# H_bridge_v2.net
KiCad netlist of a schematic drawn in Altium Designer
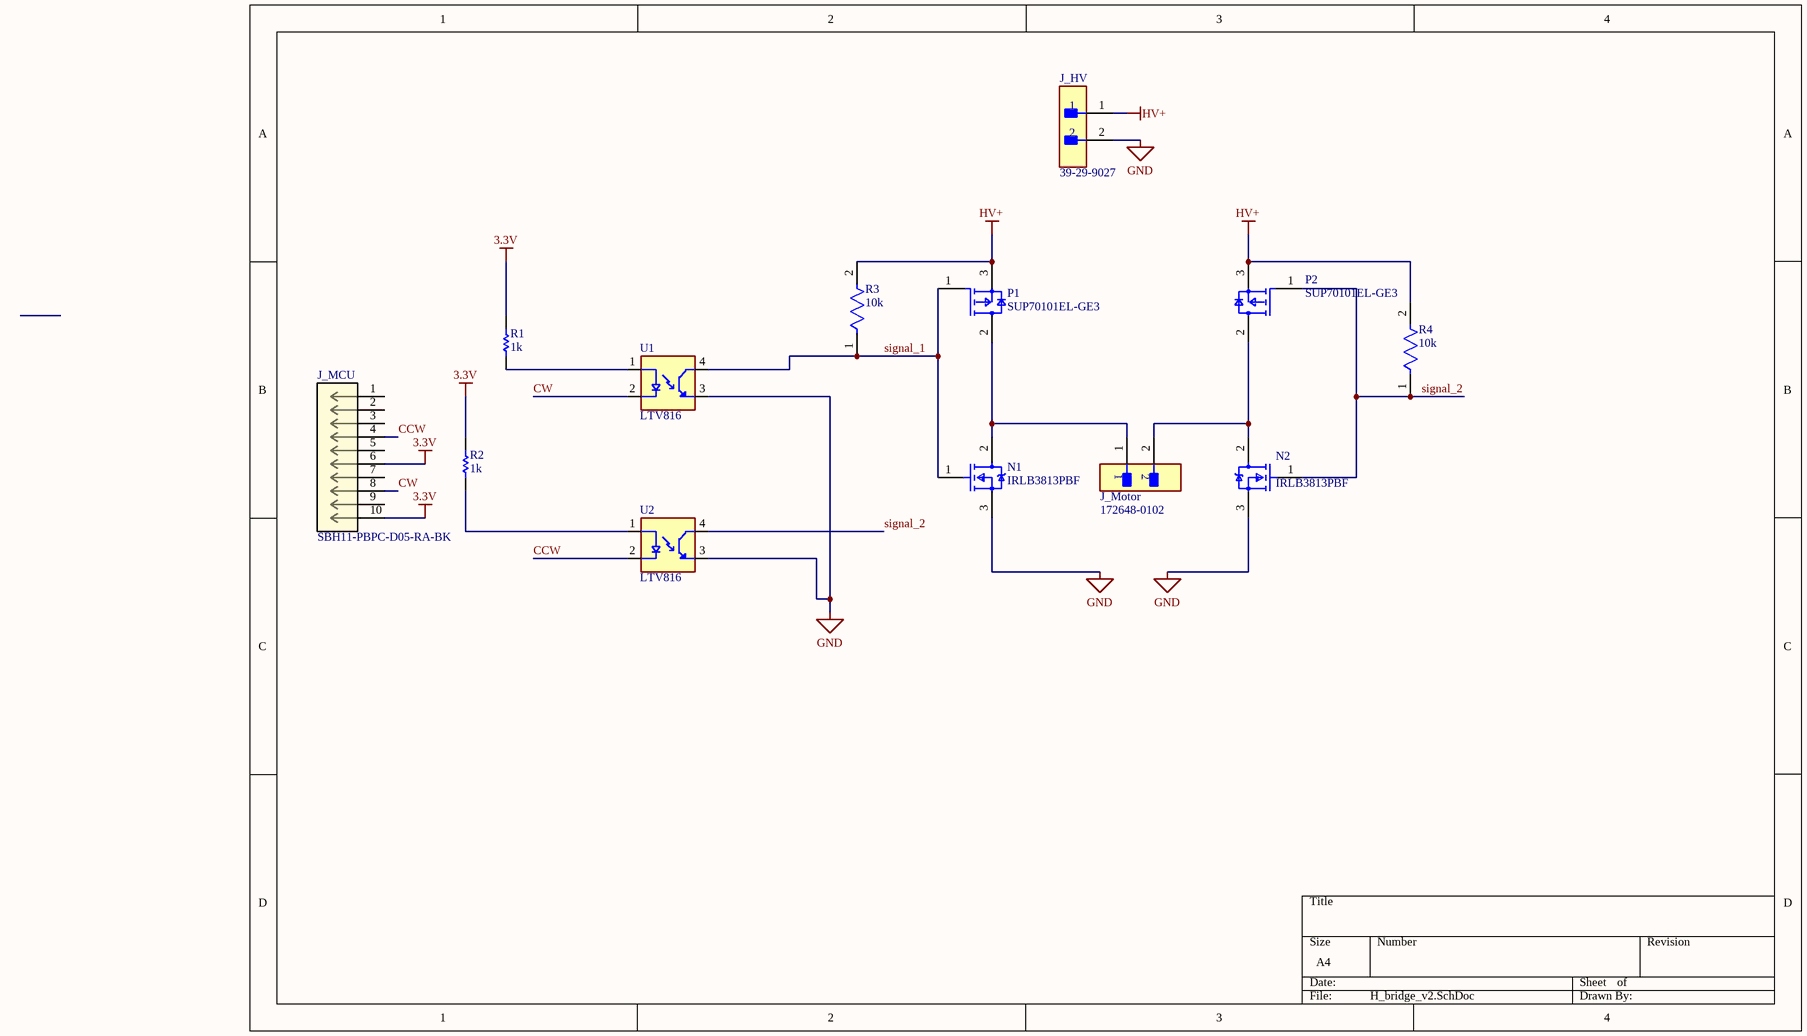
[diagram p0: H_bridge_v2.SchDoc]

(export (version "E")
  (design (tool "Eeschema 10.0.6"))
  (components
    (comp (ref "J_HV")
      (value "39-29-9027")
      (footprint "FP-39-29-9027-MFG")
      (description "CONN HEADER VERT 2POS")
      (libsource (lib "Altium Content Vault") (part "3bc925449376181038e59eaffc5286c"))
    )
    (comp (ref "J_MCU")
      (value "SBH11-PBPC-D05-RA-BK")
      (footprint "CONN10_D05-RA-BK_SUL")
      (description "Description")
      (fields (field (name "COPYRIGHT") "Copyright (C) 2026 Ultra Librarian. All rights reserved."))
      (libsource (lib "SBH11-PBPC-D05-RA-BK_MINE") (part "SBH11-PBPC-D05-RA-BK"))
    )
    (comp (ref "J_Motor")
      (value "172648-0102")
      (footprint "FP-172648-0102-MFG")
      (description "CONN HEADER R/A 2POS 4.2MM")
      (libsource (lib "Altium Content Vault") (part "88c1139f9d239099ffebecbe3f7647a"))
    )
    (comp (ref "N1")
      (value "IRLB3813PBF")
      (footprint "FP-PG-TO220-3-MFG")
      (description "MOSFET N-CH 30V 260A TO-220AB")
      (fields
        (field (name "OCTOPART") "https://octopart.com/irlb3813pbf-infineon-65874923")
        (field (name "MANUFACTURER") "Infineon")
      )
      (libsource (lib "Altium Content Vault") (part "b09f7f152735e370c1ea22a33fa83d6"))
    )
    (comp (ref "N2")
      (value "IRLB3813PBF")
      (footprint "FP-PG-TO220-3-MFG")
      (description "MOSFET N-CH 30V 260A TO-220AB")
      (fields
        (field (name "OCTOPART") "https://octopart.com/irlb3813pbf-infineon-65874923")
        (field (name "MANUFACTURER") "Infineon")
      )
      (libsource (lib "Altium Content Vault") (part "b09f7f152735e370c1ea22a33fa83d6"))
    )
    (comp (ref "P1")
      (value "SUP70101EL-GE3")
      (footprint "FP-SUP70101EL-GE3-MFG")
      (description "MOSFET P-CH 100V 120A TO220AB")
      (fields
        (field (name "OCTOPART") "https://octopart.com/sup70101el-ge3-vishay-82190902")
        (field (name "MANUFACTURER") "Vishay")
      )
      (libsource (lib "Altium Content Vault") (part "63ad6933b9e4fbdba174d6934cad31e"))
    )
    (comp (ref "P2")
      (value "SUP70101EL-GE3")
      (footprint "FP-SUP70101EL-GE3-MFG")
      (description "MOSFET P-CH 100V 120A TO220AB")
      (fields
        (field (name "OCTOPART") "https://octopart.com/sup70101el-ge3-vishay-82190902")
        (field (name "MANUFACTURER") "Vishay")
      )
      (libsource (lib "Altium Content Vault") (part "63ad6933b9e4fbdba174d6934cad31e"))
    )
    (comp (ref "R1")
      (value "1k")
      (footprint "RESA60-630X240")
      (description "Axial Resistor, 1 KOhm, +/- 1%, 250 mW, -55 to 155 degC, 2-Pin THD, RoHS, Bulk")
      (fields (field (name "TOLERANCE") "1%"))
      (libsource (lib "Altium Content Vault") (part "RES-2"))
    )
    (comp (ref "R2")
      (value "1k")
      (footprint "RESA60-630X240")
      (description "Axial Resistor, 1 KOhm, +/- 1%, 250 mW, -55 to 155 degC, 2-Pin THD, RoHS, Bulk")
      (fields (field (name "TOLERANCE") "1%"))
      (libsource (lib "Altium Content Vault") (part "RES-2"))
    )
    (comp (ref "R3")
      (value "10k")
      (footprint "FP-MF0207-MFG")
      (description "RES 10K OHM 1% 0.6W AXIAL")
      (fields (field (name "TOLERANCE") "1%"))
      (libsource (lib "Altium Content Vault") (part "1029c3af85768c4190bb7ad29bc67b5"))
    )
    (comp (ref "R4")
      (value "10k")
      (footprint "FP-MF0207-MFG")
      (description "RES 10K OHM 1% 0.6W AXIAL")
      (fields (field (name "TOLERANCE") "1%"))
      (libsource (lib "Altium Content Vault") (part "1029c3af85768c4190bb7ad29bc67b5"))
    )
    (comp (ref "U1")
      (value "LTV816")
      (footprint "DIP762W50P254L460H450Q4")
      (fields (field (name "MF") "{'manufacturer': u'Lite-On Inc.'}"))
      (libsource (lib "LTV816") (part "LTV816"))
    )
    (comp (ref "U2")
      (value "LTV816")
      (footprint "DIP762W50P254L460H450Q4")
      (fields (field (name "MF") "{'manufacturer': u'Lite-On Inc.'}"))
      (libsource (lib "LTV816") (part "LTV816"))
    )
  )
  (nets
    (net (code "1") (name "/CCW") (class "Default")
      (node (ref "J_MCU") (pin "4") (pinfunction "4_4") (pintype "passive"))
      (node (ref "U2") (pin "2") (pinfunction "C_2") (pintype "passive"))
    )
    (net (code "2") (name "/CW") (class "Default")
      (node (ref "J_MCU") (pin "8") (pinfunction "8_8") (pintype "passive"))
      (node (ref "U1") (pin "2") (pinfunction "C_2") (pintype "passive"))
    )
    (net (code "3") (name "/signal_1") (class "Default")
      (node (ref "N1") (pin "1") (pinfunction "G_1") (pintype "passive"))
      (node (ref "P1") (pin "1") (pinfunction "G_1") (pintype "passive"))
      (node (ref "R3") (pin "1") (pinfunction "1_1") (pintype "passive"))
      (node (ref "U1") (pin "4") (pinfunction "CT_4") (pintype "passive"))
    )
    (net (code "4") (name "/signal_2") (class "Default")
      (node (ref "N2") (pin "1") (pinfunction "G_1") (pintype "passive"))
      (node (ref "P2") (pin "1") (pinfunction "G_1") (pintype "passive"))
      (node (ref "R4") (pin "1") (pinfunction "1_1") (pintype "passive"))
      (node (ref "U2") (pin "4") (pinfunction "CT_4") (pintype "passive"))
    )
    (net (code "5") (name "3.3V") (class "Default")
      (node (ref "J_MCU") (pin "10") (pinfunction "10_10") (pintype "passive"))
      (node (ref "J_MCU") (pin "6") (pinfunction "6_6") (pintype "passive"))
      (node (ref "R1") (pin "2") (pinfunction "2_2") (pintype "passive"))
      (node (ref "R2") (pin "2") (pinfunction "2_2") (pintype "passive"))
    )
    (net (code "6") (name "GND") (class "Default")
      (node (ref "J_HV") (pin "2") (pinfunction "2_2") (pintype "passive"))
      (node (ref "N1") (pin "3") (pinfunction "S_3") (pintype "passive"))
      (node (ref "N2") (pin "3") (pinfunction "S_3") (pintype "passive"))
      (node (ref "U1") (pin "3") (pinfunction "ET_3") (pintype "passive"))
      (node (ref "U2") (pin "3") (pinfunction "ET_3") (pintype "passive"))
    )
    (net (code "7") (name "HV+") (class "Default")
      (node (ref "J_HV") (pin "1") (pinfunction "1_1") (pintype "passive"))
      (node (ref "P1") (pin "3") (pinfunction "S_3") (pintype "passive"))
      (node (ref "P2") (pin "3") (pinfunction "S_3") (pintype "passive"))
      (node (ref "R3") (pin "2") (pinfunction "2_2") (pintype "passive"))
      (node (ref "R4") (pin "2") (pinfunction "2_2") (pintype "passive"))
    )
    (net (code "8") (name "Net-(N1-D)") (class "Default")
      (node (ref "J_Motor") (pin "1") (pinfunction "1_1") (pintype "passive"))
      (node (ref "N1") (pin "2") (pinfunction "D_2") (pintype "passive"))
      (node (ref "P1") (pin "2") (pinfunction "D_2") (pintype "passive"))
    )
    (net (code "9") (name "Net-(N2-D)") (class "Default")
      (node (ref "J_Motor") (pin "2") (pinfunction "2_2") (pintype "passive"))
      (node (ref "N2") (pin "2") (pinfunction "D_2") (pintype "passive"))
      (node (ref "P2") (pin "2") (pinfunction "D_2") (pintype "passive"))
    )
    (net (code "10") (name "Net-(U1-A)") (class "Default")
      (node (ref "R1") (pin "1") (pinfunction "1_1") (pintype "passive"))
      (node (ref "U1") (pin "1") (pinfunction "A_1") (pintype "passive"))
    )
    (net (code "11") (name "Net-(U2-A)") (class "Default")
      (node (ref "R2") (pin "1") (pinfunction "1_1") (pintype "passive"))
      (node (ref "U2") (pin "1") (pinfunction "A_1") (pintype "passive"))
    )
    (net (code "12") (name "unconnected-(J_MCU-Pad1)") (class "Default")
      (node (ref "J_MCU") (pin "1") (pinfunction "1_1") (pintype "passive"))
    )
    (net (code "13") (name "unconnected-(J_MCU-Pad2)") (class "Default")
      (node (ref "J_MCU") (pin "2") (pinfunction "2_2") (pintype "passive"))
    )
    (net (code "14") (name "unconnected-(J_MCU-Pad3)") (class "Default")
      (node (ref "J_MCU") (pin "3") (pinfunction "3_3") (pintype "passive"))
    )
    (net (code "15") (name "unconnected-(J_MCU-Pad5)") (class "Default")
      (node (ref "J_MCU") (pin "5") (pinfunction "5_5") (pintype "passive"))
    )
    (net (code "16") (name "unconnected-(J_MCU-Pad7)") (class "Default")
      (node (ref "J_MCU") (pin "7") (pinfunction "7_7") (pintype "passive"))
    )
    (net (code "17") (name "unconnected-(J_MCU-Pad9)") (class "Default")
      (node (ref "J_MCU") (pin "9") (pinfunction "9_9") (pintype "passive"))
    )
  )
)
